# M_ni_1.net
KiCad netlist of a schematic drawn in EasyEDA
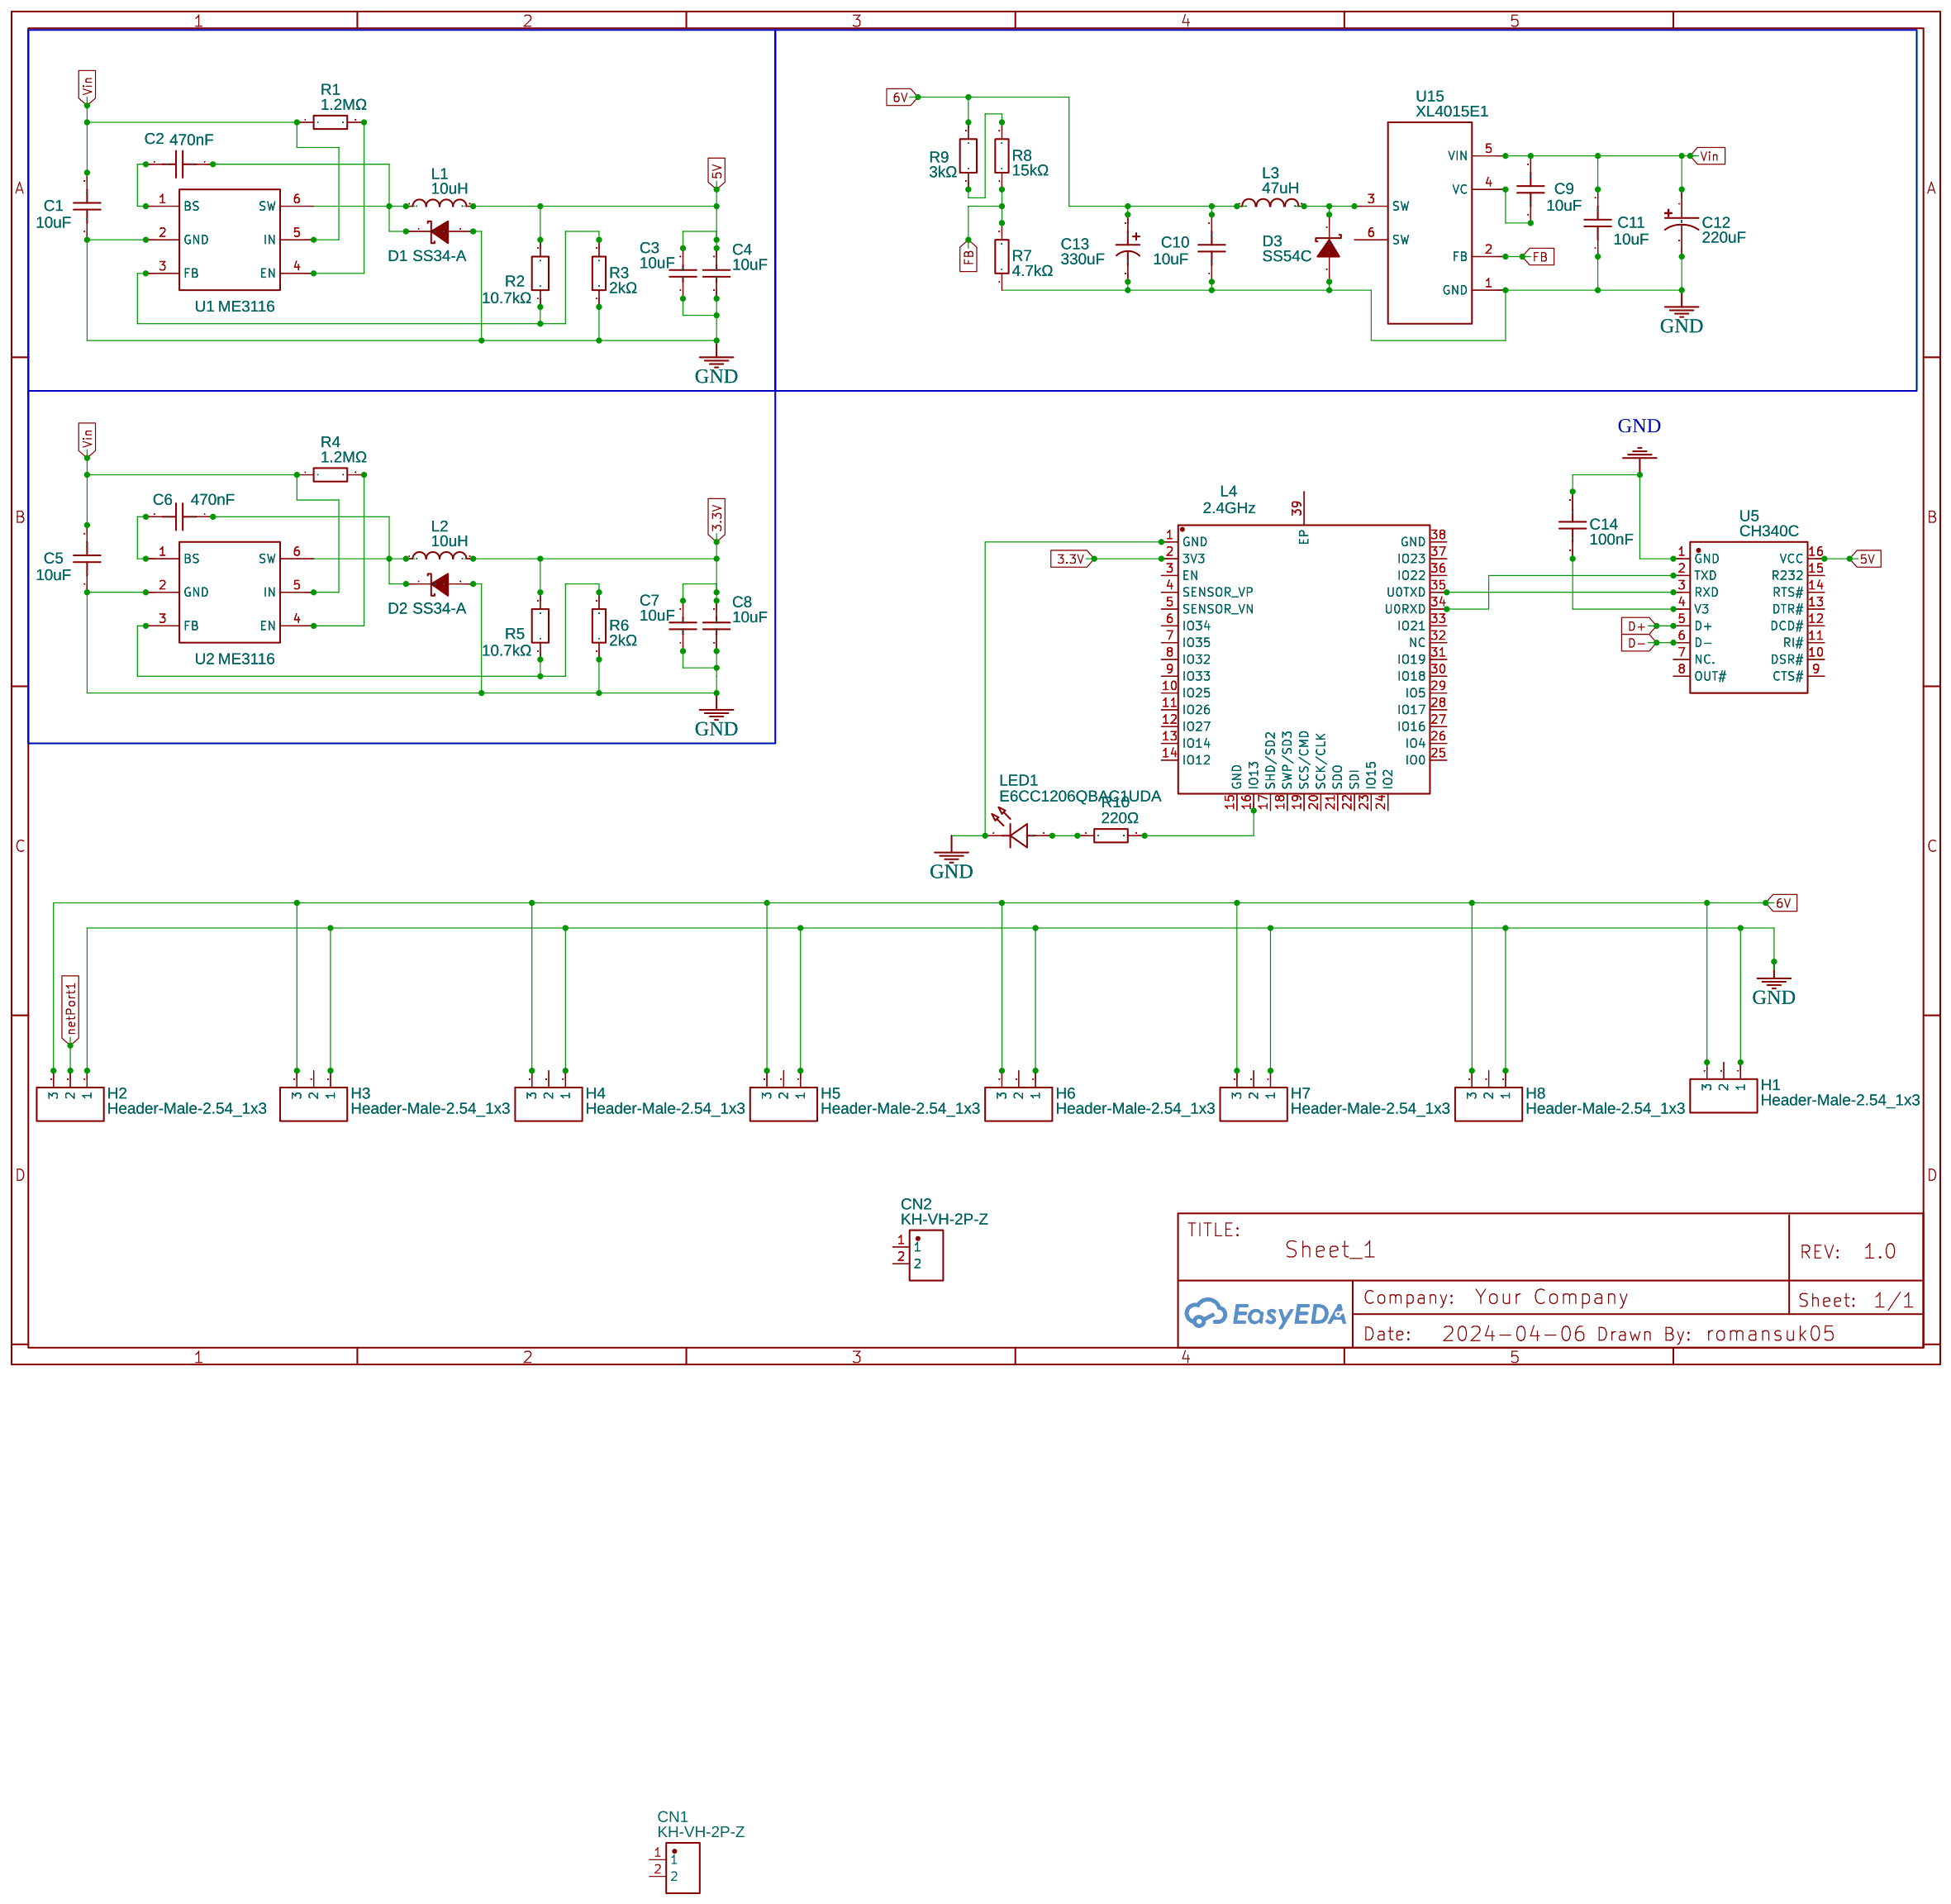
[diagram p0: schematic sheet]

(export (version "E")
  (design (tool "Eeschema 10.0.6"))
  (components
    (comp (ref "C1")
      (value "10uF")
      (fields
        (field (name "Manufacturer Part") "TCC1206X7R106K250HT")
        (field (name "Manufacturer") "CCTC(三环)")
      )
      (libsource (lib "") (part "TCC1206X7R106K250HT"))
    )
    (comp (ref "C2")
      (value "470nF")
      (fields
        (field (name "Manufacturer Part") "TCC1206X7R474K500FT")
        (field (name "Manufacturer") "CCTC(三环)")
      )
      (libsource (lib "") (part "TCC1206X7R474K500FT"))
    )
    (comp (ref "C3")
      (value "10uF")
      (fields
        (field (name "Manufacturer Part") "TMK316B7106KL-TD")
        (field (name "Manufacturer") "TAIYO YUDEN(太诱)")
      )
      (libsource (lib "") (part "TMK316B7106KL-TD"))
    )
    (comp (ref "C4")
      (value "10uF")
      (fields
        (field (name "Manufacturer Part") "TMK316B7106KL-TD")
        (field (name "Manufacturer") "TAIYO YUDEN(太诱)")
      )
      (libsource (lib "") (part "TMK316B7106KL-TD"))
    )
    (comp (ref "C5")
      (value "10uF")
      (fields
        (field (name "Manufacturer Part") "TCC1206X7R106K250HT")
        (field (name "Manufacturer") "CCTC(三环)")
      )
      (libsource (lib "") (part "TCC1206X7R106K250HT"))
    )
    (comp (ref "C6")
      (value "470nF")
      (fields
        (field (name "Manufacturer Part") "TCC1206X7R474K500FT")
        (field (name "Manufacturer") "CCTC(三环)")
      )
      (libsource (lib "") (part "TCC1206X7R474K500FT"))
    )
    (comp (ref "C7")
      (value "10uF")
      (fields
        (field (name "Manufacturer Part") "TMK316B7106KL-TD")
        (field (name "Manufacturer") "TAIYO YUDEN(太诱)")
      )
      (libsource (lib "") (part "TMK316B7106KL-TD"))
    )
    (comp (ref "C8")
      (value "10uF")
      (fields
        (field (name "Manufacturer Part") "TMK316B7106KL-TD")
        (field (name "Manufacturer") "TAIYO YUDEN(太诱)")
      )
      (libsource (lib "") (part "TMK316B7106KL-TD"))
    )
    (comp (ref "C9")
      (value "10uF")
      (fields
        (field (name "Manufacturer Part") "TCC1206X7R106K250HT")
        (field (name "Manufacturer") "CCTC(三环)")
      )
      (libsource (lib "") (part "TCC1206X7R106K250HT"))
    )
    (comp (ref "C10")
      (value "10uF")
      (fields
        (field (name "Manufacturer Part") "TCC1206X7R106K250HT")
        (field (name "Manufacturer") "CCTC(三环)")
      )
      (libsource (lib "") (part "TCC1206X7R106K250HT"))
    )
    (comp (ref "C11")
      (value "10uF")
      (fields
        (field (name "Manufacturer Part") "TCC1206X7R106K250HT")
        (field (name "Manufacturer") "CCTC(三环)")
      )
      (libsource (lib "") (part "TCC1206X7R106K250HT"))
    )
    (comp (ref "C12")
      (value "220uF")
      (fields
        (field (name "Manufacturer Part") "BXJ50V220M10*10 10TP")
        (field (name "Manufacturer") "SAMYOUNG(韩国三莹)")
      )
      (libsource (lib "") (part "BXJ-50V220-10*10"))
    )
    (comp (ref "C13")
      (value "330uF")
      (fields (field (name "Manufacturer Part") "189RV0016") (field (name "Manufacturer") "KNSCHA(科尼盛)"))
      (libsource (lib "") (part "189RV0016"))
    )
    (comp (ref "C14")
      (value "100nF")
      (fields
        (field (name "Manufacturer Part") "1206Y1000104KXR")
        (field (name "Manufacturer") "Knowles(楼氏)")
      )
      (libsource (lib "") (part "1206Y1000104KXR"))
    )
    (comp (ref "CN1")
      (value "KH-VH-2P-Z")
      (fields (field (name "Manufacturer") "kinghelm(金航标)"))
      (libsource (lib "") (part "KH-VH-2P-Z"))
    )
    (comp (ref "CN2")
      (value "KH-VH-2P-Z")
      (fields (field (name "Manufacturer") "kinghelm(金航标)"))
      (libsource (lib "") (part "KH-VH-2P-Z"))
    )
    (comp (ref "D1")
      (value "SS34-A")
      (fields (field (name "Manufacturer") "FMS(美丽微)"))
      (libsource (lib "") (part "SS34-A"))
    )
    (comp (ref "D2")
      (value "SS34-A")
      (fields (field (name "Manufacturer") "FMS(美丽微)"))
      (libsource (lib "") (part "SS34-A"))
    )
    (comp (ref "D3")
      (value "SS54C")
      (fields (field (name "Manufacturer Part") "SS54") (field (name "Manufacturer") "LGE(鲁光)"))
      (libsource (lib "") (part "SS54C"))
    )
    (comp (ref "H1")
      (value "Header-Male-2.54_1x3")
      (fields (field (name "Manufacturer Part") "2.54-1*3P针") (field (name "Manufacturer") "BOOMELE(博穆精密)"))
      (libsource (lib "") (part "Header-Male-2.54_1x3"))
    )
    (comp (ref "H2")
      (value "Header-Male-2.54_1x3")
      (fields (field (name "Manufacturer Part") "2.54-1*3P针") (field (name "Manufacturer") "BOOMELE(博穆精密)"))
      (libsource (lib "") (part "Header-Male-2.54_1x3"))
    )
    (comp (ref "H3")
      (value "Header-Male-2.54_1x3")
      (fields (field (name "Manufacturer Part") "2.54-1*3P针") (field (name "Manufacturer") "BOOMELE(博穆精密)"))
      (libsource (lib "") (part "Header-Male-2.54_1x3"))
    )
    (comp (ref "H4")
      (value "Header-Male-2.54_1x3")
      (fields (field (name "Manufacturer Part") "2.54-1*3P针") (field (name "Manufacturer") "BOOMELE(博穆精密)"))
      (libsource (lib "") (part "Header-Male-2.54_1x3"))
    )
    (comp (ref "H5")
      (value "Header-Male-2.54_1x3")
      (fields (field (name "Manufacturer Part") "2.54-1*3P针") (field (name "Manufacturer") "BOOMELE(博穆精密)"))
      (libsource (lib "") (part "Header-Male-2.54_1x3"))
    )
    (comp (ref "H6")
      (value "Header-Male-2.54_1x3")
      (fields (field (name "Manufacturer Part") "2.54-1*3P针") (field (name "Manufacturer") "BOOMELE(博穆精密)"))
      (libsource (lib "") (part "Header-Male-2.54_1x3"))
    )
    (comp (ref "H7")
      (value "Header-Male-2.54_1x3")
      (fields (field (name "Manufacturer Part") "2.54-1*3P针") (field (name "Manufacturer") "BOOMELE(博穆精密)"))
      (libsource (lib "") (part "Header-Male-2.54_1x3"))
    )
    (comp (ref "H8")
      (value "Header-Male-2.54_1x3")
      (fields (field (name "Manufacturer Part") "2.54-1*3P针") (field (name "Manufacturer") "BOOMELE(博穆精密)"))
      (libsource (lib "") (part "Header-Male-2.54_1x3"))
    )
    (comp (ref "L1")
      (value "10uH")
      (fields (field (name "Manufacturer Part") "CY75SX-10UH") (field (name "Manufacturer") "SHOU HAN(首韩)"))
      (libsource (lib "") (part "CY75SX-10UH"))
    )
    (comp (ref "L2")
      (value "10uH")
      (fields (field (name "Manufacturer Part") "CY75SX-10UH") (field (name "Manufacturer") "SHOU HAN(首韩)"))
      (libsource (lib "") (part "CY75SX-10UH"))
    )
    (comp (ref "L3")
      (value "47uH")
      (fields (field (name "Manufacturer Part") "GCCD4532N-470M01") (field (name "Manufacturer") "GLE(格莱尔)"))
      (libsource (lib "") (part "GCD43-470MC"))
    )
    (comp (ref "L4")
      (value "2.4GHz")
      (fields
        (field (name "Manufacturer Part") "ESP32-S(16MB)")
        (field (name "Manufacturer") "Ai-Thinker(安信可)")
      )
      (libsource (lib "") (part "ESP32-S(16MB)"))
    )
    (comp (ref "LED1")
      (value "E6CC1206QBAC1UDA")
      (fields (field (name "Manufacturer") "ekinglux(亿晶源)"))
      (libsource (lib "") (part "E6CC1206QBAC1UDA"))
    )
    (comp (ref "R1")
      (value "1.2MΩ")
      (fields (field (name "Manufacturer Part") "WR12W1204FTL") (field (name "Manufacturer") "Walsin(华新科)"))
      (libsource (lib "") (part "WR12W1204FTL"))
    )
    (comp (ref "R2")
      (value "10.7kΩ")
      (fields (field (name "Manufacturer Part") "RC1206FR-0710K7L") (field (name "Manufacturer") "YAGEO(国巨)"))
      (libsource (lib "") (part "RC1206FR-0710K7L"))
    )
    (comp (ref "R3")
      (value "2kΩ")
      (fields (field (name "Manufacturer Part") "RTT06202JTP") (field (name "Manufacturer") "RALEC(旺诠)"))
      (libsource (lib "") (part "RTT06202JTP"))
    )
    (comp (ref "R4")
      (value "1.2MΩ")
      (fields (field (name "Manufacturer Part") "WR12W1204FTL") (field (name "Manufacturer") "Walsin(华新科)"))
      (libsource (lib "") (part "WR12W1204FTL"))
    )
    (comp (ref "R5")
      (value "10.7kΩ")
      (fields (field (name "Manufacturer Part") "RC1206FR-0710K7L") (field (name "Manufacturer") "YAGEO(国巨)"))
      (libsource (lib "") (part "RC1206FR-0710K7L"))
    )
    (comp (ref "R6")
      (value "2kΩ")
      (fields (field (name "Manufacturer Part") "RTT06202JTP") (field (name "Manufacturer") "RALEC(旺诠)"))
      (libsource (lib "") (part "RTT06202JTP"))
    )
    (comp (ref "R7")
      (value "4.7kΩ")
      (fields
        (field (name "Manufacturer Part") "CRCW12064K70FKEA")
        (field (name "Manufacturer") "VISHAY(威世)")
      )
      (libsource (lib "") (part "CRCW12064K70FKEA"))
    )
    (comp (ref "R8")
      (value "15kΩ")
      (fields (field (name "Manufacturer Part") "RT1206FRD0715KL") (field (name "Manufacturer") "YAGEO(国巨)"))
      (libsource (lib "") (part "RT1206FRD0715KL"))
    )
    (comp (ref "R9")
      (value "3kΩ")
      (fields
        (field (name "Manufacturer Part") "CR1206J3K00P05Z")
        (field (name "Manufacturer") "EVER OHMS(天二科技)")
      )
      (libsource (lib "") (part "CR1206J3K00P05Z"))
    )
    (comp (ref "R10")
      (value "220Ω")
      (fields (field (name "Manufacturer Part") "CR1206F42200G") (field (name "Manufacturer") "LIZ(丽智电子)"))
      (libsource (lib "") (part "CR1206F42200G"))
    )
    (comp (ref "U1")
      (value "ME3116")
      (fields (field (name "Manufacturer Part") "ME3116AM6G") (field (name "Manufacturer") "MICRONE(南京微盟)"))
      (libsource (lib "") (part "ME3116"))
    )
    (comp (ref "U2")
      (value "ME3116")
      (fields (field (name "Manufacturer Part") "ME3116AM6G") (field (name "Manufacturer") "MICRONE(南京微盟)"))
      (libsource (lib "") (part "ME3116"))
    )
    (comp (ref "U5")
      (value "CH340C")
      (fields (field (name "Manufacturer") "WCH(南京沁恒)"))
      (libsource (lib "") (part "CH340C"))
    )
    (comp (ref "U15")
      (value "XL4015E1")
      (fields (field (name "Manufacturer") "XLSEMI(芯龙)"))
      (libsource (lib "") (part "XL4015E1"))
    )
  )
  (nets
    (net (code "1") (name "3.3V") (class "Default")
      (node (ref "C7") (pin "2") (pinfunction "2_2") (pintype "input"))
      (node (ref "C8") (pin "2") (pinfunction "2_2") (pintype "input"))
      (node (ref "L2") (pin "2") (pinfunction "2_2") (pintype "unspecified"))
      (node (ref "L4") (pin "2") (pinfunction "3V3_2") (pintype "unspecified"))
      (node (ref "R5") (pin "2") (pinfunction "2_2") (pintype "unspecified"))
    )
    (net (code "2") (name "5V") (class "Default")
      (node (ref "C3") (pin "2") (pinfunction "2_2") (pintype "input"))
      (node (ref "C4") (pin "2") (pinfunction "2_2") (pintype "input"))
      (node (ref "L1") (pin "2") (pinfunction "2_2") (pintype "unspecified"))
      (node (ref "R2") (pin "2") (pinfunction "2_2") (pintype "unspecified"))
      (node (ref "U5") (pin "16") (pinfunction "VCC_16") (pintype "unspecified"))
    )
    (net (code "3") (name "6V") (class "Default")
      (node (ref "C10") (pin "2") (pinfunction "2_2") (pintype "unspecified"))
      (node (ref "C13") (pin "1") (pinfunction "1_1") (pintype "input"))
      (node (ref "H1") (pin "3") (pinfunction "3_3") (pintype "input"))
      (node (ref "H2") (pin "3") (pinfunction "3_3") (pintype "input"))
      (node (ref "H3") (pin "3") (pinfunction "3_3") (pintype "input"))
      (node (ref "H4") (pin "3") (pinfunction "3_3") (pintype "input"))
      (node (ref "H5") (pin "3") (pinfunction "3_3") (pintype "input"))
      (node (ref "H6") (pin "3") (pinfunction "3_3") (pintype "input"))
      (node (ref "H7") (pin "3") (pinfunction "3_3") (pintype "input"))
      (node (ref "H8") (pin "3") (pinfunction "3_3") (pintype "input"))
      (node (ref "L3") (pin "1") (pinfunction "1_1") (pintype "unspecified"))
      (node (ref "R9") (pin "2") (pinfunction "2_2") (pintype "unspecified"))
    )
    (net (code "4") (name "D+") (class "Default")
      (node (ref "U5") (pin "5") (pinfunction "D+_5") (pintype "unspecified"))
    )
    (net (code "5") (name "D-") (class "Default")
      (node (ref "U5") (pin "6") (pinfunction "D-_6") (pintype "unspecified"))
    )
    (net (code "6") (name "FB") (class "Default")
      (node (ref "R7") (pin "2") (pinfunction "2_2") (pintype "unspecified"))
      (node (ref "R8") (pin "1") (pinfunction "1_1") (pintype "unspecified"))
      (node (ref "U15") (pin "2") (pinfunction "FB_2") (pintype "unspecified"))
    )
    (net (code "7") (name "GND") (class "Default")
      (node (ref "C1") (pin "1") (pinfunction "1_1") (pintype "unspecified"))
      (node (ref "C10") (pin "1") (pinfunction "1_1") (pintype "unspecified"))
      (node (ref "C11") (pin "1") (pinfunction "1_1") (pintype "unspecified"))
      (node (ref "C12") (pin "2") (pinfunction "2_2") (pintype "unspecified"))
      (node (ref "C13") (pin "2") (pinfunction "2_2") (pintype "input"))
      (node (ref "C14") (pin "2") (pinfunction "2_2") (pintype "unspecified"))
      (node (ref "C3") (pin "1") (pinfunction "1_1") (pintype "input"))
      (node (ref "C4") (pin "1") (pinfunction "1_1") (pintype "input"))
      (node (ref "C5") (pin "1") (pinfunction "1_1") (pintype "unspecified"))
      (node (ref "C7") (pin "1") (pinfunction "1_1") (pintype "input"))
      (node (ref "C8") (pin "1") (pinfunction "1_1") (pintype "input"))
      (node (ref "D1") (pin "2") (pinfunction "A_2") (pintype "unspecified"))
      (node (ref "D2") (pin "2") (pinfunction "A_2") (pintype "unspecified"))
      (node (ref "D3") (pin "2") (pinfunction "A_2") (pintype "unspecified"))
      (node (ref "H1") (pin "1") (pinfunction "1_1") (pintype "input"))
      (node (ref "H2") (pin "1") (pinfunction "1_1") (pintype "input"))
      (node (ref "H3") (pin "1") (pinfunction "1_1") (pintype "input"))
      (node (ref "H4") (pin "1") (pinfunction "1_1") (pintype "input"))
      (node (ref "H5") (pin "1") (pinfunction "1_1") (pintype "input"))
      (node (ref "H6") (pin "1") (pinfunction "1_1") (pintype "input"))
      (node (ref "H7") (pin "1") (pinfunction "1_1") (pintype "input"))
      (node (ref "H8") (pin "1") (pinfunction "1_1") (pintype "input"))
      (node (ref "L4") (pin "1") (pinfunction "GND_1") (pintype "unspecified"))
      (node (ref "LED1") (pin "1") (pinfunction "K_1") (pintype "unspecified"))
      (node (ref "R3") (pin "1") (pinfunction "1_1") (pintype "input"))
      (node (ref "R6") (pin "1") (pinfunction "1_1") (pintype "input"))
      (node (ref "R7") (pin "1") (pinfunction "1_1") (pintype "unspecified"))
      (node (ref "U1") (pin "2") (pinfunction "GND_2") (pintype "unspecified"))
      (node (ref "U15") (pin "1") (pinfunction "GND_1") (pintype "unspecified"))
      (node (ref "U2") (pin "2") (pinfunction "GND_2") (pintype "unspecified"))
      (node (ref "U5") (pin "1") (pinfunction "GND_1") (pintype "unspecified"))
    )
    (net (code "8") (name "Net-(D1-C)") (class "Default")
      (node (ref "C2") (pin "1") (pinfunction "1_1") (pintype "unspecified"))
      (node (ref "D1") (pin "1") (pinfunction "C_1") (pintype "unspecified"))
      (node (ref "L1") (pin "1") (pinfunction "1_1") (pintype "unspecified"))
      (node (ref "U1") (pin "6") (pinfunction "SW_6") (pintype "unspecified"))
    )
    (net (code "9") (name "Net-(D2-C)") (class "Default")
      (node (ref "C6") (pin "1") (pinfunction "1_1") (pintype "unspecified"))
      (node (ref "D2") (pin "1") (pinfunction "C_1") (pintype "unspecified"))
      (node (ref "L2") (pin "1") (pinfunction "1_1") (pintype "unspecified"))
      (node (ref "U2") (pin "6") (pinfunction "SW_6") (pintype "unspecified"))
    )
    (net (code "10") (name "Net-(D3-K)") (class "Default")
      (node (ref "D3") (pin "1") (pinfunction "K_1") (pintype "unspecified"))
      (node (ref "L3") (pin "2") (pinfunction "2_2") (pintype "unspecified"))
      (node (ref "U15") (pin "3") (pinfunction "SW_3") (pintype "unspecified"))
    )
    (net (code "11") (name "Net-(L4-IO13)") (class "Default")
      (node (ref "L4") (pin "16") (pinfunction "IO13_16") (pintype "unspecified"))
      (node (ref "R10") (pin "2") (pinfunction "2_2") (pintype "input"))
    )
    (net (code "12") (name "Net-(L4-U0RXD)") (class "Default")
      (node (ref "L4") (pin "34") (pinfunction "U0RXD_34") (pintype "unspecified"))
      (node (ref "U5") (pin "2") (pinfunction "TXD_2") (pintype "unspecified"))
    )
    (net (code "13") (name "Net-(L4-U0TXD)") (class "Default")
      (node (ref "L4") (pin "35") (pinfunction "U0TXD_35") (pintype "unspecified"))
      (node (ref "U5") (pin "3") (pinfunction "RXD_3") (pintype "unspecified"))
    )
    (net (code "14") (name "Net-(LED1-A)") (class "Default")
      (node (ref "LED1") (pin "2") (pinfunction "A_2") (pintype "unspecified"))
      (node (ref "R10") (pin "1") (pinfunction "1_1") (pintype "input"))
    )
    (net (code "15") (name "Net-(R8-Pad2)") (class "Default")
      (node (ref "R8") (pin "2") (pinfunction "2_2") (pintype "unspecified"))
      (node (ref "R9") (pin "1") (pinfunction "1_1") (pintype "unspecified"))
    )
    (net (code "16") (name "Net-(U1-BS)") (class "Default")
      (node (ref "C2") (pin "2") (pinfunction "2_2") (pintype "unspecified"))
      (node (ref "U1") (pin "1") (pinfunction "BS_1") (pintype "unspecified"))
    )
    (net (code "17") (name "Net-(U1-EN)") (class "Default")
      (node (ref "R1") (pin "2") (pinfunction "2_2") (pintype "unspecified"))
      (node (ref "U1") (pin "4") (pinfunction "EN_4") (pintype "unspecified"))
    )
    (net (code "18") (name "Net-(U1-FB)") (class "Default")
      (node (ref "R2") (pin "1") (pinfunction "1_1") (pintype "unspecified"))
      (node (ref "R3") (pin "2") (pinfunction "2_2") (pintype "input"))
      (node (ref "U1") (pin "3") (pinfunction "FB_3") (pintype "unspecified"))
    )
    (net (code "19") (name "Net-(U2-BS)") (class "Default")
      (node (ref "C6") (pin "2") (pinfunction "2_2") (pintype "unspecified"))
      (node (ref "U2") (pin "1") (pinfunction "BS_1") (pintype "unspecified"))
    )
    (net (code "20") (name "Net-(U2-EN)") (class "Default")
      (node (ref "R4") (pin "2") (pinfunction "2_2") (pintype "unspecified"))
      (node (ref "U2") (pin "4") (pinfunction "EN_4") (pintype "unspecified"))
    )
    (net (code "21") (name "Net-(U2-FB)") (class "Default")
      (node (ref "R5") (pin "1") (pinfunction "1_1") (pintype "unspecified"))
      (node (ref "R6") (pin "2") (pinfunction "2_2") (pintype "input"))
      (node (ref "U2") (pin "3") (pinfunction "FB_3") (pintype "unspecified"))
    )
    (net (code "22") (name "Net-(U5-V3)") (class "Default")
      (node (ref "C14") (pin "1") (pinfunction "1_1") (pintype "unspecified"))
      (node (ref "U5") (pin "4") (pinfunction "V3_4") (pintype "unspecified"))
    )
    (net (code "23") (name "Net-(U15-VC)") (class "Default")
      (node (ref "C9") (pin "1") (pinfunction "1_1") (pintype "unspecified"))
      (node (ref "U15") (pin "4") (pinfunction "VC_4") (pintype "unspecified"))
    )
    (net (code "24") (name "Vin") (class "Default")
      (node (ref "C1") (pin "2") (pinfunction "2_2") (pintype "unspecified"))
      (node (ref "C11") (pin "2") (pinfunction "2_2") (pintype "unspecified"))
      (node (ref "C12") (pin "1") (pinfunction "1_1") (pintype "unspecified"))
      (node (ref "C5") (pin "2") (pinfunction "2_2") (pintype "unspecified"))
      (node (ref "C9") (pin "2") (pinfunction "2_2") (pintype "unspecified"))
      (node (ref "R1") (pin "1") (pinfunction "1_1") (pintype "unspecified"))
      (node (ref "R4") (pin "1") (pinfunction "1_1") (pintype "unspecified"))
      (node (ref "U1") (pin "5") (pinfunction "IN_5") (pintype "unspecified"))
      (node (ref "U15") (pin "5") (pinfunction "VIN_5") (pintype "unspecified"))
      (node (ref "U2") (pin "5") (pinfunction "IN_5") (pintype "unspecified"))
    )
    (net (code "25") (name "netPort1") (class "Default")
      (node (ref "H2") (pin "2") (pinfunction "2_2") (pintype "input"))
    )
    (net (code "26") (name "unconnected-(CN1-Pad1)") (class "Default")
      (node (ref "CN1") (pin "1") (pinfunction "1_1") (pintype "unspecified"))
    )
    (net (code "27") (name "unconnected-(CN1-Pad2)") (class "Default")
      (node (ref "CN1") (pin "2") (pinfunction "2_2") (pintype "unspecified"))
    )
    (net (code "28") (name "unconnected-(CN2-Pad1)") (class "Default")
      (node (ref "CN2") (pin "1") (pinfunction "1_1") (pintype "unspecified"))
    )
    (net (code "29") (name "unconnected-(CN2-Pad2)") (class "Default")
      (node (ref "CN2") (pin "2") (pinfunction "2_2") (pintype "unspecified"))
    )
    (net (code "30") (name "unconnected-(H1-Pad2)") (class "Default")
      (node (ref "H1") (pin "2") (pinfunction "2_2") (pintype "input"))
    )
    (net (code "31") (name "unconnected-(H3-Pad2)") (class "Default")
      (node (ref "H3") (pin "2") (pinfunction "2_2") (pintype "input"))
    )
    (net (code "32") (name "unconnected-(H4-Pad2)") (class "Default")
      (node (ref "H4") (pin "2") (pinfunction "2_2") (pintype "input"))
    )
    (net (code "33") (name "unconnected-(H5-Pad2)") (class "Default")
      (node (ref "H5") (pin "2") (pinfunction "2_2") (pintype "input"))
    )
    (net (code "34") (name "unconnected-(H6-Pad2)") (class "Default")
      (node (ref "H6") (pin "2") (pinfunction "2_2") (pintype "input"))
    )
    (net (code "35") (name "unconnected-(H7-Pad2)") (class "Default")
      (node (ref "H7") (pin "2") (pinfunction "2_2") (pintype "input"))
    )
    (net (code "36") (name "unconnected-(H8-Pad2)") (class "Default")
      (node (ref "H8") (pin "2") (pinfunction "2_2") (pintype "input"))
    )
    (net (code "37") (name "unconnected-(L4-EN-Pad3)") (class "Default")
      (node (ref "L4") (pin "3") (pinfunction "EN_3") (pintype "unspecified"))
    )
    (net (code "38") (name "unconnected-(L4-EP-Pad39)") (class "Default")
      (node (ref "L4") (pin "39") (pinfunction "EP_39") (pintype "unspecified"))
    )
    (net (code "39") (name "unconnected-(L4-GND-Pad15)") (class "Default")
      (node (ref "L4") (pin "15") (pinfunction "GND_15") (pintype "unspecified"))
    )
    (net (code "40") (name "unconnected-(L4-GND-Pad38)") (class "Default")
      (node (ref "L4") (pin "38") (pinfunction "GND_38") (pintype "unspecified"))
    )
    (net (code "41") (name "unconnected-(L4-IO0-Pad25)") (class "Default")
      (node (ref "L4") (pin "25") (pinfunction "IO0_25") (pintype "unspecified"))
    )
    (net (code "42") (name "unconnected-(L4-IO2-Pad24)") (class "Default")
      (node (ref "L4") (pin "24") (pinfunction "IO2_24") (pintype "unspecified"))
    )
    (net (code "43") (name "unconnected-(L4-IO4-Pad26)") (class "Default")
      (node (ref "L4") (pin "26") (pinfunction "IO4_26") (pintype "unspecified"))
    )
    (net (code "44") (name "unconnected-(L4-IO5-Pad29)") (class "Default")
      (node (ref "L4") (pin "29") (pinfunction "IO5_29") (pintype "unspecified"))
    )
    (net (code "45") (name "unconnected-(L4-IO12-Pad14)") (class "Default")
      (node (ref "L4") (pin "14") (pinfunction "IO12_14") (pintype "unspecified"))
    )
    (net (code "46") (name "unconnected-(L4-IO14-Pad13)") (class "Default")
      (node (ref "L4") (pin "13") (pinfunction "IO14_13") (pintype "unspecified"))
    )
    (net (code "47") (name "unconnected-(L4-IO15-Pad23)") (class "Default")
      (node (ref "L4") (pin "23") (pinfunction "IO15_23") (pintype "unspecified"))
    )
    (net (code "48") (name "unconnected-(L4-IO16-Pad27)") (class "Default")
      (node (ref "L4") (pin "27") (pinfunction "IO16_27") (pintype "unspecified"))
    )
    (net (code "49") (name "unconnected-(L4-IO17-Pad28)") (class "Default")
      (node (ref "L4") (pin "28") (pinfunction "IO17_28") (pintype "unspecified"))
    )
    (net (code "50") (name "unconnected-(L4-IO18-Pad30)") (class "Default")
      (node (ref "L4") (pin "30") (pinfunction "IO18_30") (pintype "unspecified"))
    )
    (net (code "51") (name "unconnected-(L4-IO19-Pad31)") (class "Default")
      (node (ref "L4") (pin "31") (pinfunction "IO19_31") (pintype "unspecified"))
    )
    (net (code "52") (name "unconnected-(L4-IO21-Pad33)") (class "Default")
      (node (ref "L4") (pin "33") (pinfunction "IO21_33") (pintype "unspecified"))
    )
    (net (code "53") (name "unconnected-(L4-IO22-Pad36)") (class "Default")
      (node (ref "L4") (pin "36") (pinfunction "IO22_36") (pintype "unspecified"))
    )
    (net (code "54") (name "unconnected-(L4-IO23-Pad37)") (class "Default")
      (node (ref "L4") (pin "37") (pinfunction "IO23_37") (pintype "unspecified"))
    )
    (net (code "55") (name "unconnected-(L4-IO25-Pad10)") (class "Default")
      (node (ref "L4") (pin "10") (pinfunction "IO25_10") (pintype "unspecified"))
    )
    (net (code "56") (name "unconnected-(L4-IO26-Pad11)") (class "Default")
      (node (ref "L4") (pin "11") (pinfunction "IO26_11") (pintype "unspecified"))
    )
    (net (code "57") (name "unconnected-(L4-IO27-Pad12)") (class "Default")
      (node (ref "L4") (pin "12") (pinfunction "IO27_12") (pintype "unspecified"))
    )
    (net (code "58") (name "unconnected-(L4-IO32-Pad8)") (class "Default")
      (node (ref "L4") (pin "8") (pinfunction "IO32_8") (pintype "unspecified"))
    )
    (net (code "59") (name "unconnected-(L4-IO33-Pad9)") (class "Default")
      (node (ref "L4") (pin "9") (pinfunction "IO33_9") (pintype "unspecified"))
    )
    (net (code "60") (name "unconnected-(L4-IO34-Pad6)") (class "Default")
      (node (ref "L4") (pin "6") (pinfunction "IO34_6") (pintype "unspecified"))
    )
    (net (code "61") (name "unconnected-(L4-IO35-Pad7)") (class "Default")
      (node (ref "L4") (pin "7") (pinfunction "IO35_7") (pintype "unspecified"))
    )
    (net (code "62") (name "unconnected-(L4-NC-Pad32)") (class "Default")
      (node (ref "L4") (pin "32") (pinfunction "NC_32") (pintype "unspecified"))
    )
    (net (code "63") (name "unconnected-(L4-SCK{slash}CLK-Pad20)") (class "Default")
      (node (ref "L4") (pin "20") (pinfunction "SCK/CLK_20") (pintype "unspecified"))
    )
    (net (code "64") (name "unconnected-(L4-SCS{slash}CMD-Pad19)") (class "Default")
      (node (ref "L4") (pin "19") (pinfunction "SCS/CMD_19") (pintype "unspecified"))
    )
    (net (code "65") (name "unconnected-(L4-SDI-Pad22)") (class "Default")
      (node (ref "L4") (pin "22") (pinfunction "SDI_22") (pintype "unspecified"))
    )
    (net (code "66") (name "unconnected-(L4-SDO-Pad21)") (class "Default")
      (node (ref "L4") (pin "21") (pinfunction "SDO_21") (pintype "unspecified"))
    )
    (net (code "67") (name "unconnected-(L4-SENSOR_VN-Pad5)") (class "Default")
      (node (ref "L4") (pin "5") (pinfunction "SENSOR_VN_5") (pintype "unspecified"))
    )
    (net (code "68") (name "unconnected-(L4-SENSOR_VP-Pad4)") (class "Default")
      (node (ref "L4") (pin "4") (pinfunction "SENSOR_VP_4") (pintype "unspecified"))
    )
    (net (code "69") (name "unconnected-(L4-SHD{slash}SD2-Pad17)") (class "Default")
      (node (ref "L4") (pin "17") (pinfunction "SHD/SD2_17") (pintype "unspecified"))
    )
    (net (code "70") (name "unconnected-(L4-SWP{slash}SD3-Pad18)") (class "Default")
      (node (ref "L4") (pin "18") (pinfunction "SWP/SD3_18") (pintype "unspecified"))
    )
    (net (code "71") (name "unconnected-(U5-CTS#-Pad9)") (class "Default")
      (node (ref "U5") (pin "9") (pinfunction "CTS#_9") (pintype "unspecified"))
    )
    (net (code "72") (name "unconnected-(U5-DCD#-Pad12)") (class "Default")
      (node (ref "U5") (pin "12") (pinfunction "DCD#_12") (pintype "unspecified"))
    )
    (net (code "73") (name "unconnected-(U5-DSR#-Pad10)") (class "Default")
      (node (ref "U5") (pin "10") (pinfunction "DSR#_10") (pintype "unspecified"))
    )
    (net (code "74") (name "unconnected-(U5-DTR#-Pad13)") (class "Default")
      (node (ref "U5") (pin "13") (pinfunction "DTR#_13") (pintype "unspecified"))
    )
    (net (code "75") (name "unconnected-(U5-NC.-Pad7)") (class "Default")
      (node (ref "U5") (pin "7") (pinfunction "NC._7") (pintype "unspecified"))
    )
    (net (code "76") (name "unconnected-(U5-OUT#-Pad8)") (class "Default")
      (node (ref "U5") (pin "8") (pinfunction "OUT#_8") (pintype "unspecified"))
    )
    (net (code "77") (name "unconnected-(U5-R232-Pad15)") (class "Default")
      (node (ref "U5") (pin "15") (pinfunction "R232_15") (pintype "unspecified"))
    )
    (net (code "78") (name "unconnected-(U5-RI#-Pad11)") (class "Default")
      (node (ref "U5") (pin "11") (pinfunction "RI#_11") (pintype "unspecified"))
    )
    (net (code "79") (name "unconnected-(U5-RTS#-Pad14)") (class "Default")
      (node (ref "U5") (pin "14") (pinfunction "RTS#_14") (pintype "unspecified"))
    )
    (net (code "80") (name "unconnected-(U15-SW-Pad6)") (class "Default")
      (node (ref "U15") (pin "6") (pinfunction "SW_6") (pintype "unspecified"))
    )
  )
)
